# OpAmpGndOut.net
KiCad netlist of a schematic drawn in Altium Designer
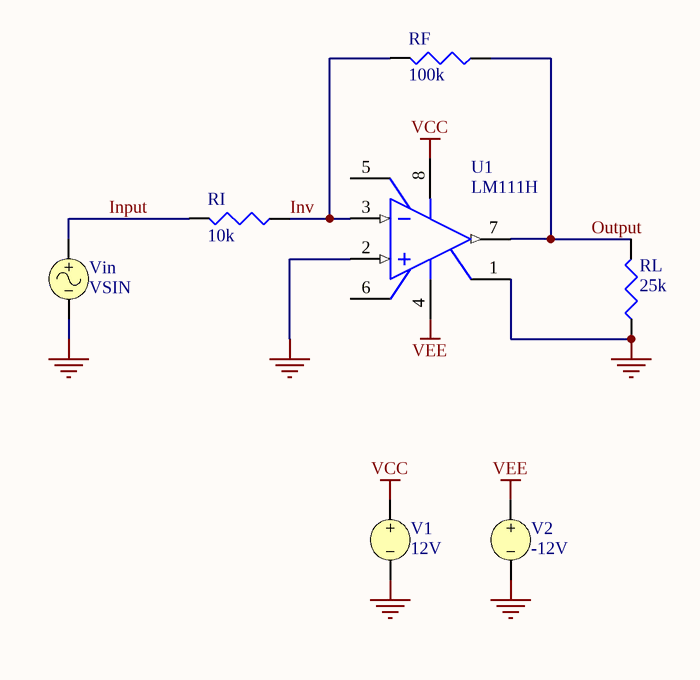
[diagram p0: OpAmpGndOut.schdoc]

(export (version "E")
  (design (tool "Eeschema 10.0.6"))
  (components
    (comp (ref "RF") (value "100k") (description "Resistor") (libsource (lib "*") (part "RES")))
    (comp (ref "RI") (value "10k") (description "Resistor") (libsource (lib "*") (part "RES")))
    (comp (ref "RL") (value "25k") (description "Resistor") (libsource (lib "") (part "RES_1")))
    (comp (ref "U1")
      (value "LM111H")
      (footprint "H08C")
      (description "Voltage Comparator")
      (fields
        (field (name "MANUFACTURER") "National Semiconductor")
        (field (name "DIGIKEYPARTNUMBER") "LM111H-ND")
        (field (name "PUBLISHER") "Altium Limited")
      )
      (libsource (lib "NSC Amplifier with SIM models") (part "LM111H"))
    )
    (comp (ref "V1") (value "12V") (description "Voltage Source") (libsource (lib "*") (part "VSRC")))
    (comp (ref "V2") (value "-12V") (description "Voltage Source") (libsource (lib "*") (part "VSRC")))
    (comp (ref "Vin")
      (value "VSIN")
      (description "Sinusoidal Voltage Source")
      (libsource (lib "*") (part "VSIN"))
    )
  )
  (nets
    (net (code "1") (name "/Input") (class "Default")
      (node (ref "RI") (pin "1") (pinfunction "TOP_1") (pintype "passive"))
      (node (ref "Vin") (pin "1") (pinfunction "1_1") (pintype "passive"))
    )
    (net (code "2") (name "/Inv") (class "Default")
      (node (ref "RF") (pin "1") (pinfunction "TOP_1") (pintype "passive"))
      (node (ref "RI") (pin "2") (pinfunction "BOT_2") (pintype "passive"))
      (node (ref "U1") (pin "3") (pinfunction "IN-_3") (pintype "input"))
    )
    (net (code "3") (name "/Output") (class "Default")
      (node (ref "RF") (pin "2") (pinfunction "BOT_2") (pintype "passive"))
      (node (ref "RL") (pin "1") (pinfunction "TOP_1") (pintype "passive"))
      (node (ref "U1") (pin "7") (pinfunction "OUT_7") (pintype "output"))
    )
    (net (code "4") (name "GND") (class "Default")
      (node (ref "RL") (pin "2") (pinfunction "BOT_2") (pintype "passive"))
      (node (ref "U1") (pin "1") (pinfunction "GND_1") (pintype "power_in"))
      (node (ref "U1") (pin "2") (pinfunction "IN+_2") (pintype "input"))
      (node (ref "V1") (pin "2") (pinfunction "2_2") (pintype "passive"))
      (node (ref "V2") (pin "2") (pinfunction "2_2") (pintype "passive"))
      (node (ref "Vin") (pin "2") (pinfunction "2_2") (pintype "passive"))
    )
    (net (code "5") (name "VCC") (class "Default")
      (node (ref "U1") (pin "8") (pinfunction "V+_8") (pintype "power_in"))
      (node (ref "V1") (pin "1") (pinfunction "1_1") (pintype "passive"))
    )
    (net (code "6") (name "VEE") (class "Default")
      (node (ref "U1") (pin "4") (pinfunction "V-_4") (pintype "power_in"))
      (node (ref "V2") (pin "1") (pinfunction "1_1") (pintype "passive"))
    )
    (net (code "7") (name "unconnected-(U1-BAL-Pad5)") (class "Default")
      (node (ref "U1") (pin "5") (pinfunction "BAL_5") (pintype "passive"))
    )
    (net (code "8") (name "unconnected-(U1-BAL{slash}STB-Pad6)") (class "Default")
      (node (ref "U1") (pin "6") (pinfunction "BAL/STB_6") (pintype "passive"))
    )
  )
)
